# OLED_Display.net
KiCad netlist of a schematic drawn in EAGLE
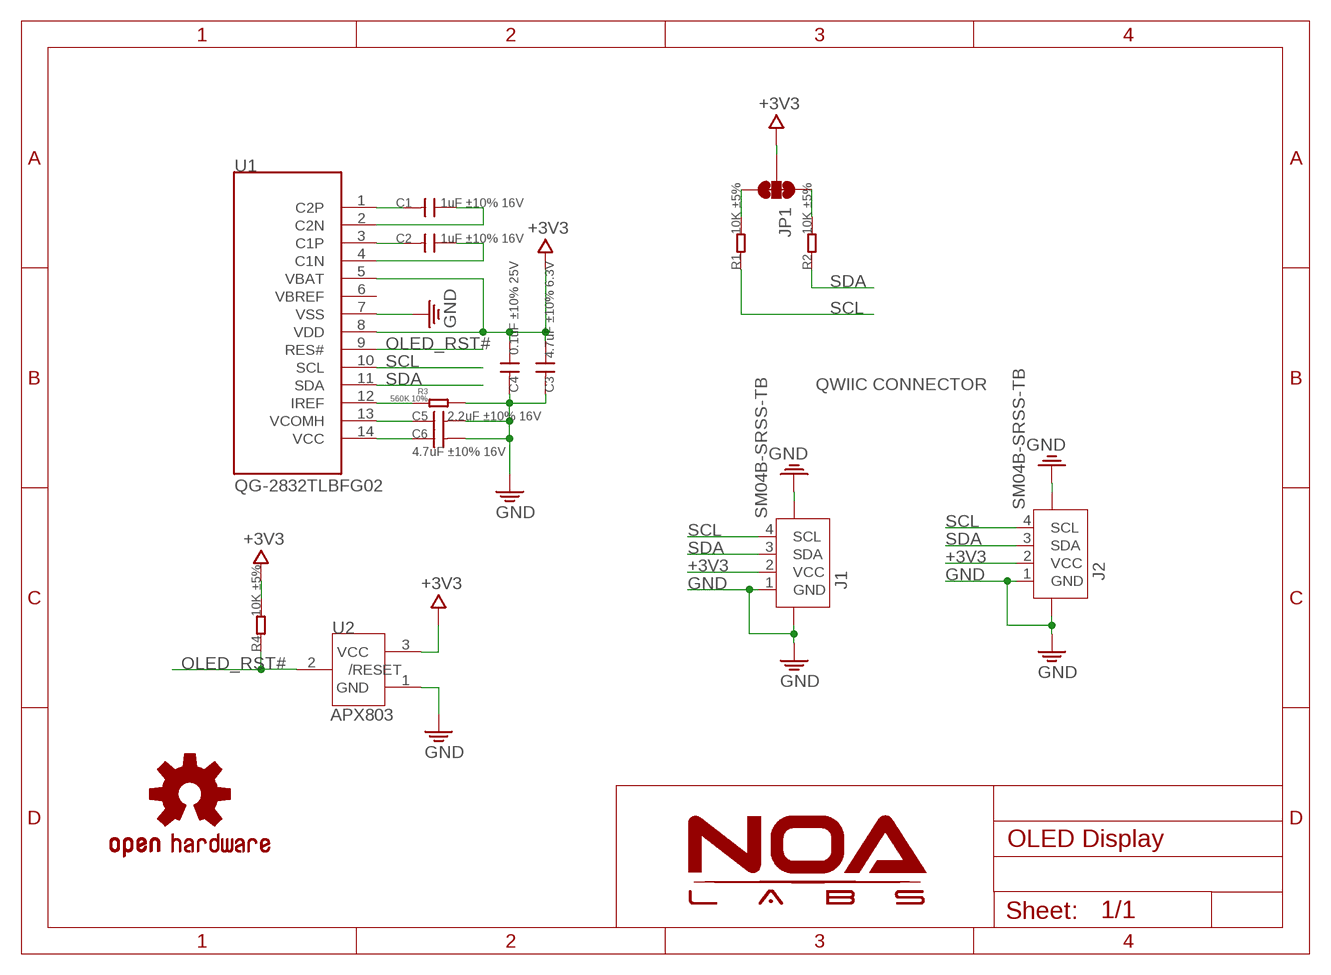
[diagram p0: schematic, sheet 1]

(export (version "E")
  (design (tool "Eeschema 10.0.6"))
  (components
    (comp (ref "C1")
      (value "1uF ±10% 16V")
      (footprint "eagle-import:0603")
      (libsource (lib "eagle-import") (part "C-0603"))
    )
    (comp (ref "C2")
      (value "1uF ±10% 16V")
      (footprint "eagle-import:0603")
      (libsource (lib "eagle-import") (part "C-0603"))
    )
    (comp (ref "C3")
      (value "4.7uF ±10% 6.3V")
      (footprint "eagle-import:0603")
      (libsource (lib "eagle-import") (part "C-0603"))
    )
    (comp (ref "C4")
      (value "0.1uF ±10% 25V")
      (footprint "eagle-import:0603")
      (libsource (lib "eagle-import") (part "C-0603"))
    )
    (comp (ref "C5")
      (value "2.2uF ±10% 16V")
      (footprint "eagle-import:0603")
      (libsource (lib "eagle-import") (part "C-0603"))
    )
    (comp (ref "C6")
      (value "4.7uF ±10% 16V")
      (footprint "eagle-import:0603")
      (libsource (lib "eagle-import") (part "C-0603"))
    )
    (comp (ref "J1")
      (value "SM04B-SRSS-TB")
      (footprint "eagle-import:JST-SH-4P")
      (libsource (lib "eagle-import") (part "JST-SH-4P-1.0"))
    )
    (comp (ref "J2")
      (value "SM04B-SRSS-TB")
      (footprint "eagle-import:JST-SH-4P")
      (libsource (lib "eagle-import") (part "JST-SH-4P-1.0"))
    )
    (comp (ref "JP1")
      (value "SMT-JUMPER_3_2-NC_TRACE")
      (footprint "eagle-import:SMT-JUMPER_3_2-NC_TRACE")
      (libsource (lib "eagle-import") (part "SMT-JUMPER_3_2-NC_TRACE"))
    )
    (comp (ref "LOGO2")
      (value "OSHW-LOGOMINI")
      (footprint "eagle-import:OSHW-LOGO-MINI")
      (libsource (lib "eagle-import") (part "OSHW-LOGOMINI"))
    )
    (comp (ref "R1")
      (value "10K ±5%")
      (footprint "eagle-import:0603")
      (libsource (lib "eagle-import") (part "R-0603"))
    )
    (comp (ref "R2")
      (value "10K ±5%")
      (footprint "eagle-import:0603")
      (libsource (lib "eagle-import") (part "R-0603"))
    )
    (comp (ref "R3")
      (value "560K 10%")
      (footprint "eagle-import:0603")
      (libsource (lib "eagle-import") (part "R-0603"))
    )
    (comp (ref "R4")
      (value "10K ±5%")
      (footprint "eagle-import:0603")
      (libsource (lib "eagle-import") (part "R-0603"))
    )
    (comp (ref "U1")
      (value "QG-2832TLBFG02")
      (footprint "eagle-import:OLED-12832")
      (libsource (lib "eagle-import") (part "OLED-12832"))
    )
    (comp (ref "U2")
      (value "APX803")
      (footprint "eagle-import:SOT23")
      (libsource (lib "eagle-import") (part "APX803"))
    )
  )
  (nets
    (net (code "1") (name "+3V3") (class "Default")
      (node (ref "C3") (pin "1") (pinfunction "1_1") (pintype "passive"))
      (node (ref "C4") (pin "1") (pinfunction "1_1") (pintype "passive"))
      (node (ref "J1") (pin "2") (pinfunction "VCC_2") (pintype "bidirectional"))
      (node (ref "J2") (pin "2") (pinfunction "VCC_2") (pintype "bidirectional"))
      (node (ref "JP1") (pin "2") (pinfunction "2_2") (pintype "passive"))
      (node (ref "R4") (pin "2") (pinfunction "2_2") (pintype "passive"))
      (node (ref "U1") (pin "5") (pinfunction "VBAT_5") (pintype "bidirectional"))
      (node (ref "U1") (pin "8") (pinfunction "VDD_8") (pintype "bidirectional"))
      (node (ref "U2") (pin "3") (pinfunction "VCC_3") (pintype "bidirectional"))
    )
    (net (code "2") (name "/OLED_RST#") (class "Default")
      (node (ref "R4") (pin "1") (pinfunction "1_1") (pintype "passive"))
      (node (ref "U1") (pin "9") (pinfunction "RES#_9") (pintype "bidirectional"))
      (node (ref "U2") (pin "2") (pinfunction "/RESET_2") (pintype "bidirectional"))
    )
    (net (code "3") (name "/SCL") (class "Default")
      (node (ref "J1") (pin "4") (pinfunction "SCL_4") (pintype "bidirectional"))
      (node (ref "J2") (pin "4") (pinfunction "SCL_4") (pintype "bidirectional"))
      (node (ref "R1") (pin "1") (pinfunction "1_1") (pintype "passive"))
      (node (ref "U1") (pin "10") (pinfunction "SCL_10") (pintype "bidirectional"))
    )
    (net (code "4") (name "/SDA") (class "Default")
      (node (ref "J1") (pin "3") (pinfunction "SDA_3") (pintype "bidirectional"))
      (node (ref "J2") (pin "3") (pinfunction "SDA_3") (pintype "bidirectional"))
      (node (ref "R2") (pin "1") (pinfunction "1_1") (pintype "passive"))
      (node (ref "U1") (pin "11") (pinfunction "SDA_11") (pintype "bidirectional"))
    )
    (net (code "5") (name "GND") (class "Default")
      (node (ref "C3") (pin "2") (pinfunction "2_2") (pintype "passive"))
      (node (ref "C4") (pin "2") (pinfunction "2_2") (pintype "passive"))
      (node (ref "C5") (pin "2") (pinfunction "2_2") (pintype "passive"))
      (node (ref "C6") (pin "2") (pinfunction "2_2") (pintype "passive"))
      (node (ref "J1") (pin "1") (pinfunction "GND_1") (pintype "bidirectional"))
      (node (ref "J1") (pin "NC1") (pinfunction "5_NC1") (pintype "bidirectional"))
      (node (ref "J1") (pin "NC2") (pinfunction "6_NC2") (pintype "bidirectional"))
      (node (ref "J2") (pin "1") (pinfunction "GND_1") (pintype "bidirectional"))
      (node (ref "J2") (pin "NC1") (pinfunction "5_NC1") (pintype "bidirectional"))
      (node (ref "J2") (pin "NC2") (pinfunction "6_NC2") (pintype "bidirectional"))
      (node (ref "R3") (pin "1") (pinfunction "1_1") (pintype "passive"))
      (node (ref "U1") (pin "7") (pinfunction "VSS_7") (pintype "bidirectional"))
      (node (ref "U2") (pin "1") (pinfunction "GND_1") (pintype "bidirectional"))
    )
    (net (code "6") (name "Net-(JP1-Pad1)") (class "Default")
      (node (ref "JP1") (pin "1") (pinfunction "1_1") (pintype "passive"))
      (node (ref "R2") (pin "2") (pinfunction "2_2") (pintype "passive"))
    )
    (net (code "7") (name "Net-(JP1-Pad3)") (class "Default")
      (node (ref "JP1") (pin "3") (pinfunction "3_3") (pintype "passive"))
      (node (ref "R1") (pin "2") (pinfunction "2_2") (pintype "passive"))
    )
    (net (code "8") (name "Net-(U1-C1N)") (class "Default")
      (node (ref "C2") (pin "1") (pinfunction "1_1") (pintype "passive"))
      (node (ref "U1") (pin "4") (pinfunction "C1N_4") (pintype "bidirectional"))
    )
    (net (code "9") (name "Net-(U1-C1P)") (class "Default")
      (node (ref "C2") (pin "2") (pinfunction "2_2") (pintype "passive"))
      (node (ref "U1") (pin "3") (pinfunction "C1P_3") (pintype "bidirectional"))
    )
    (net (code "10") (name "Net-(U1-C2N)") (class "Default")
      (node (ref "C1") (pin "1") (pinfunction "1_1") (pintype "passive"))
      (node (ref "U1") (pin "2") (pinfunction "C2N_2") (pintype "bidirectional"))
    )
    (net (code "11") (name "Net-(U1-C2P)") (class "Default")
      (node (ref "C1") (pin "2") (pinfunction "2_2") (pintype "passive"))
      (node (ref "U1") (pin "1") (pinfunction "C2P_1") (pintype "bidirectional"))
    )
    (net (code "12") (name "Net-(U1-IREF)") (class "Default")
      (node (ref "R3") (pin "2") (pinfunction "2_2") (pintype "passive"))
      (node (ref "U1") (pin "12") (pinfunction "IREF_12") (pintype "bidirectional"))
    )
    (net (code "13") (name "Net-(U1-VCC)") (class "Default")
      (node (ref "C6") (pin "1") (pinfunction "1_1") (pintype "passive"))
      (node (ref "U1") (pin "14") (pinfunction "VCC_14") (pintype "bidirectional"))
    )
    (net (code "14") (name "Net-(U1-VCOMH)") (class "Default")
      (node (ref "C5") (pin "1") (pinfunction "1_1") (pintype "passive"))
      (node (ref "U1") (pin "13") (pinfunction "VCOMH_13") (pintype "bidirectional"))
    )
    (net (code "15") (name "unconnected-(U1-VBREF-Pad6)") (class "Default")
      (node (ref "U1") (pin "6") (pinfunction "VBREF_6") (pintype "bidirectional"))
    )
  )
)
